# 07_Interface.net
KiCad netlist of a schematic drawn in Altium Designer
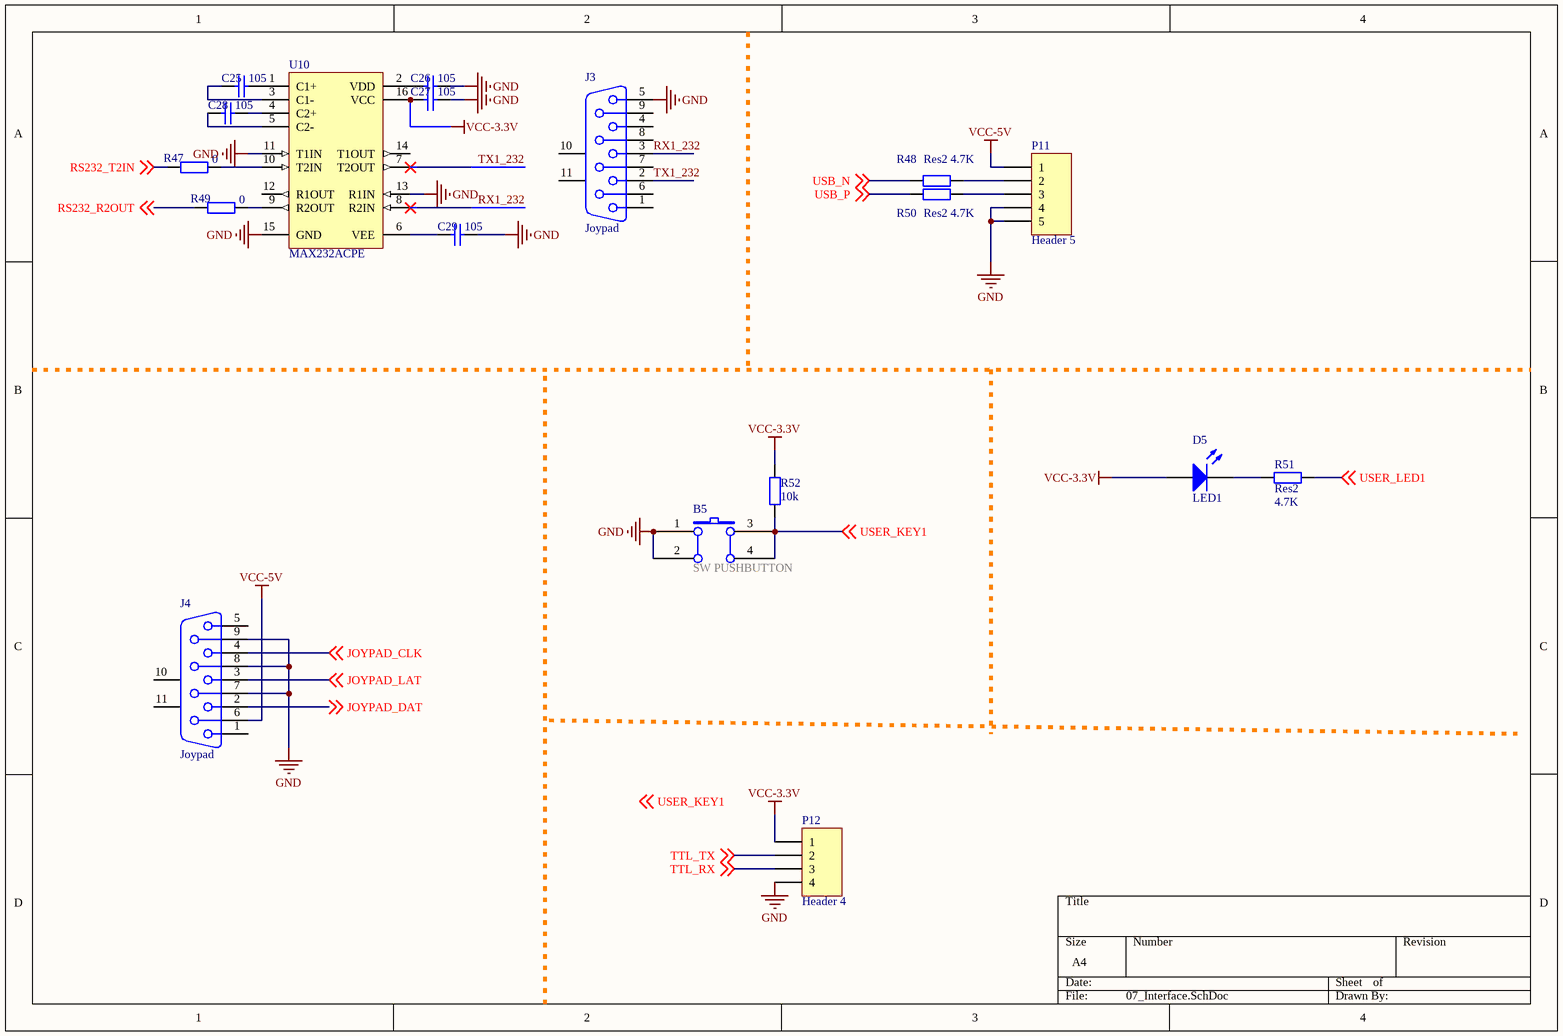
[diagram p0: 07_Interface.SchDoc]

(export (version "E")
  (design (tool "Eeschema 10.0.6"))
  (components
    (comp (ref "B5")
      (value "SW PUSHBUTTON")
      (footprint "Miscellaneous Modules:SWITCH-0.65/0.45")
      (description "Tactile Switch")
      (libsource (lib "Miscellaneous Modules") (part "SW PUSHBUTTON"))
    )
    (comp (ref "C25")
      (value "105")
      (footprint "RAD-0.1")
      (description "Capacitor")
      (fields (field (name "PUBLISHER") "Altium Limited"))
      (libsource (lib "HLK-RM04_KIT-V2.3") (part "Cap"))
    )
    (comp (ref "C26")
      (value "105")
      (footprint "RAD-0.1")
      (description "Capacitor")
      (fields (field (name "PUBLISHER") "Altium Limited"))
      (libsource (lib "HLK-RM04_KIT-V2.3") (part "Cap"))
    )
    (comp (ref "C27")
      (value "105")
      (footprint "RAD-0.1")
      (description "Capacitor")
      (fields (field (name "PUBLISHER") "Altium Limited"))
      (libsource (lib "HLK-RM04_KIT-V2.3") (part "Cap"))
    )
    (comp (ref "C28")
      (value "105")
      (footprint "RAD-0.1")
      (description "Capacitor")
      (fields (field (name "PUBLISHER") "Altium Limited"))
      (libsource (lib "HLK-RM04_KIT-V2.3") (part "Cap"))
    )
    (comp (ref "C29")
      (value "105")
      (footprint "RAD-0.1")
      (description "Capacitor")
      (fields (field (name "PUBLISHER") "Altium Limited"))
      (libsource (lib "HLK-RM04_KIT-V2.3") (part "Cap"))
    )
    (comp (ref "D5")
      (value "LED1")
      (footprint "LED-R3.0")
      (description "Typical RED GaAs LED")
      (fields (field (name "PUBLISHER") "Altium Limited"))
      (libsource (lib "Miscellaneous Devices") (part "LED1"))
    )
    (comp (ref "J3")
      (value "Joypad")
      (footprint "DSUB1.385-2H9")
      (description "Receptacle Assembly, 9 Position, Right Angle")
      (fields (field (name "PUBLISHER") "Altium Limited"))
      (libsource (lib "Miscellaneous Connectors") (part "D Connector 9"))
    )
    (comp (ref "J4")
      (value "Joypad")
      (footprint "DSUB1.385-2H9")
      (description "Receptacle Assembly, 9 Position, Right Angle")
      (fields (field (name "PUBLISHER") "Altium Limited"))
      (libsource (lib "Miscellaneous Connectors") (part "D Connector 9"))
    )
    (comp (ref "P11")
      (value "Header 5")
      (footprint "MICRO_USB")
      (description "Header, 5-Pin")
      (fields (field (name "PUBLISHER") "Altium Limited"))
      (libsource (lib "Miscellaneous Connectors") (part "Header 5"))
    )
    (comp (ref "P12")
      (value "Header 4")
      (footprint "HDR1X4")
      (description "Header, 4-Pin")
      (fields (field (name "PUBLISHER") "Altium Limited"))
      (libsource (lib "Miscellaneous Connectors") (part "Header 4"))
    )
    (comp (ref "R47")
      (value "0")
      (footprint "AXIAL-0.3")
      (description "Resistor")
      (fields (field (name "PUBLISHER") "Altium Limited"))
      (libsource (lib "HLK-RM04_KIT-V2.3") (part "Res2"))
    )
    (comp (ref "R48")
      (value "Res2")
      (footprint "AXIAL-0.3")
      (description "Resistor")
      (fields (field (name "ALTIUM_VALUE") "4.7K") (field (name "PUBLISHER") "Altium Limited"))
      (libsource (lib "Miscellaneous Devices") (part "Res2"))
    )
    (comp (ref "R49")
      (value "0")
      (footprint "AXIAL-0.3")
      (description "Resistor")
      (fields (field (name "PUBLISHER") "Altium Limited"))
      (libsource (lib "HLK-RM04_KIT-V2.3") (part "Res2"))
    )
    (comp (ref "R50")
      (value "Res2")
      (footprint "AXIAL-0.3")
      (description "Resistor")
      (fields (field (name "ALTIUM_VALUE") "4.7K") (field (name "PUBLISHER") "Altium Limited"))
      (libsource (lib "Miscellaneous Devices") (part "Res2"))
    )
    (comp (ref "R51")
      (value "Res2")
      (footprint "AXIAL-0.3")
      (description "Resistor")
      (fields (field (name "ALTIUM_VALUE") "4.7K") (field (name "PUBLISHER") "Altium Limited"))
      (libsource (lib "Miscellaneous Devices") (part "Res2"))
    )
    (comp (ref "R52")
      (value "10k")
      (footprint "AXIAL-0.3")
      (description "贴片电阻")
      (fields (field (name "PUBLISHER") "Altium Limited"))
      (libsource (lib "fszhang") (part "Res1"))
    )
    (comp (ref "U10")
      (value "MAX232ACPE")
      (footprint "SO-16_M")
      (description "+5V Powered, Multi-Channel RS-232 Driver/Receiver")
      (fields (field (name "PUBLISHER") "Altium Limited"))
      (libsource (lib "HLK-RM04_KIT-V2.3") (part "MAX232ACPE"))
    )
  )
  (nets
    (net (code "1") (name "/RX1_232") (class "Default")
      (node (ref "J3") (pin "3") (pinfunction "3_3") (pintype "passive"))
      (node (ref "U10") (pin "8") (pinfunction "R2IN_8") (pintype "input"))
    )
    (net (code "2") (name "/TX1_232") (class "Default")
      (node (ref "J3") (pin "2") (pinfunction "2_2") (pintype "passive"))
      (node (ref "U10") (pin "7") (pinfunction "T2OUT_7") (pintype "output"))
    )
    (net (code "3") (name "GND") (class "Default")
      (node (ref "B5") (pin "1") (pinfunction "A0_1") (pintype "passive"))
      (node (ref "B5") (pin "2") (pinfunction "B0_2") (pintype "passive"))
      (node (ref "C26") (pin "2") (pinfunction "2_2") (pintype "passive"))
      (node (ref "C27") (pin "2") (pinfunction "2_2") (pintype "passive"))
      (node (ref "C29") (pin "2") (pinfunction "2_2") (pintype "passive"))
      (node (ref "J3") (pin "5") (pinfunction "5_5") (pintype "passive"))
      (node (ref "J4") (pin "7") (pinfunction "7_7") (pintype "passive"))
      (node (ref "J4") (pin "8") (pinfunction "8_8") (pintype "passive"))
      (node (ref "J4") (pin "9") (pinfunction "9_9") (pintype "passive"))
      (node (ref "P11") (pin "4") (pinfunction "4_4") (pintype "passive"))
      (node (ref "P11") (pin "5") (pinfunction "5_5") (pintype "passive"))
      (node (ref "P12") (pin "4") (pinfunction "4_4") (pintype "passive"))
      (node (ref "U10") (pin "11") (pinfunction "T1IN_11") (pintype "input"))
      (node (ref "U10") (pin "13") (pinfunction "R1IN_13") (pintype "input"))
      (node (ref "U10") (pin "15") (pinfunction "GND_15") (pintype "power_in"))
    )
    (net (code "4") (name "JOYPAD_CLK") (class "Default")
      (node (ref "J4") (pin "4") (pinfunction "4_4") (pintype "passive"))
    )
    (net (code "5") (name "JOYPAD_DAT") (class "Default")
      (node (ref "J4") (pin "2") (pinfunction "2_2") (pintype "passive"))
    )
    (net (code "6") (name "JOYPAD_LAT") (class "Default")
      (node (ref "J4") (pin "3") (pinfunction "3_3") (pintype "passive"))
    )
    (net (code "7") (name "Net-(D5-K)") (class "Default")
      (node (ref "D5") (pin "2") (pinfunction "K_2") (pintype "passive"))
      (node (ref "R51") (pin "2") (pinfunction "2_2") (pintype "passive"))
    )
    (net (code "8") (name "Net-(P11-Pad2)") (class "Default")
      (node (ref "P11") (pin "2") (pinfunction "2_2") (pintype "passive"))
      (node (ref "R48") (pin "1") (pinfunction "1_1") (pintype "passive"))
    )
    (net (code "9") (name "Net-(P11-Pad3)") (class "Default")
      (node (ref "P11") (pin "3") (pinfunction "3_3") (pintype "passive"))
      (node (ref "R50") (pin "1") (pinfunction "1_1") (pintype "passive"))
    )
    (net (code "10") (name "Net-(U10-C1+)") (class "Default")
      (node (ref "C25") (pin "2") (pinfunction "2_2") (pintype "passive"))
      (node (ref "U10") (pin "1") (pinfunction "C1+_1") (pintype "passive"))
    )
    (net (code "11") (name "Net-(U10-C1-)") (class "Default")
      (node (ref "C25") (pin "1") (pinfunction "1_1") (pintype "passive"))
      (node (ref "U10") (pin "3") (pinfunction "C1-_3") (pintype "passive"))
    )
    (net (code "12") (name "Net-(U10-C2+)") (class "Default")
      (node (ref "C28") (pin "2") (pinfunction "2_2") (pintype "passive"))
      (node (ref "U10") (pin "4") (pinfunction "C2+_4") (pintype "passive"))
    )
    (net (code "13") (name "Net-(U10-C2-)") (class "Default")
      (node (ref "C28") (pin "1") (pinfunction "1_1") (pintype "passive"))
      (node (ref "U10") (pin "5") (pinfunction "C2-_5") (pintype "passive"))
    )
    (net (code "14") (name "Net-(U10-R2OUT)") (class "Default")
      (node (ref "R49") (pin "2") (pinfunction "2_2") (pintype "passive"))
      (node (ref "U10") (pin "9") (pinfunction "R2OUT_9") (pintype "output"))
    )
    (net (code "15") (name "Net-(U10-T2IN)") (class "Default")
      (node (ref "R47") (pin "2") (pinfunction "2_2") (pintype "passive"))
      (node (ref "U10") (pin "10") (pinfunction "T2IN_10") (pintype "input"))
    )
    (net (code "16") (name "Net-(U10-VDD)") (class "Default")
      (node (ref "C26") (pin "1") (pinfunction "1_1") (pintype "passive"))
      (node (ref "U10") (pin "2") (pinfunction "VDD_2") (pintype "power_in"))
    )
    (net (code "17") (name "Net-(U10-VEE)") (class "Default")
      (node (ref "C29") (pin "1") (pinfunction "1_1") (pintype "passive"))
      (node (ref "U10") (pin "6") (pinfunction "VEE_6") (pintype "power_in"))
    )
    (net (code "18") (name "RS232_R2OUT") (class "Default")
      (node (ref "R49") (pin "1") (pinfunction "1_1") (pintype "passive"))
    )
    (net (code "19") (name "RS232_T2IN") (class "Default")
      (node (ref "R47") (pin "1") (pinfunction "1_1") (pintype "passive"))
    )
    (net (code "20") (name "TTL_RX") (class "Default")
      (node (ref "P12") (pin "3") (pinfunction "3_3") (pintype "passive"))
    )
    (net (code "21") (name "TTL_TX") (class "Default")
      (node (ref "P12") (pin "2") (pinfunction "2_2") (pintype "passive"))
    )
    (net (code "22") (name "USB_N") (class "Default")
      (node (ref "R48") (pin "2") (pinfunction "2_2") (pintype "passive"))
    )
    (net (code "23") (name "USB_P") (class "Default")
      (node (ref "R50") (pin "2") (pinfunction "2_2") (pintype "passive"))
    )
    (net (code "24") (name "USER_KEY1") (class "Default")
      (node (ref "B5") (pin "3") (pinfunction "B1_3") (pintype "passive"))
      (node (ref "B5") (pin "4") (pinfunction "A1_4") (pintype "passive"))
      (node (ref "R52") (pin "1") (pinfunction "1_1") (pintype "passive"))
    )
    (net (code "25") (name "USER_LED1") (class "Default")
      (node (ref "R51") (pin "1") (pinfunction "1_1") (pintype "passive"))
    )
    (net (code "26") (name "VCC-3.3V") (class "Default")
      (node (ref "C27") (pin "1") (pinfunction "1_1") (pintype "passive"))
      (node (ref "D5") (pin "1") (pinfunction "A_1") (pintype "passive"))
      (node (ref "P12") (pin "1") (pinfunction "1_1") (pintype "passive"))
      (node (ref "R52") (pin "2") (pinfunction "2_2") (pintype "passive"))
      (node (ref "U10") (pin "16") (pinfunction "VCC_16") (pintype "power_in"))
    )
    (net (code "27") (name "VCC-5V") (class "Default")
      (node (ref "J4") (pin "6") (pinfunction "6_6") (pintype "passive"))
      (node (ref "P11") (pin "1") (pinfunction "1_1") (pintype "passive"))
    )
    (net (code "28") (name "unconnected-(J3-MH1-Pad10)") (class "Default")
      (node (ref "J3") (pin "10") (pinfunction "MH1_10") (pintype "passive"))
    )
    (net (code "29") (name "unconnected-(J3-MH2-Pad11)") (class "Default")
      (node (ref "J3") (pin "11") (pinfunction "MH2_11") (pintype "passive"))
    )
    (net (code "30") (name "unconnected-(J3-Pad1)") (class "Default")
      (node (ref "J3") (pin "1") (pinfunction "1_1") (pintype "passive"))
    )
    (net (code "31") (name "unconnected-(J3-Pad4)") (class "Default")
      (node (ref "J3") (pin "4") (pinfunction "4_4") (pintype "passive"))
    )
    (net (code "32") (name "unconnected-(J3-Pad6)") (class "Default")
      (node (ref "J3") (pin "6") (pinfunction "6_6") (pintype "passive"))
    )
    (net (code "33") (name "unconnected-(J3-Pad7)") (class "Default")
      (node (ref "J3") (pin "7") (pinfunction "7_7") (pintype "passive"))
    )
    (net (code "34") (name "unconnected-(J3-Pad8)") (class "Default")
      (node (ref "J3") (pin "8") (pinfunction "8_8") (pintype "passive"))
    )
    (net (code "35") (name "unconnected-(J3-Pad9)") (class "Default")
      (node (ref "J3") (pin "9") (pinfunction "9_9") (pintype "passive"))
    )
    (net (code "36") (name "unconnected-(J4-MH1-Pad10)") (class "Default")
      (node (ref "J4") (pin "10") (pinfunction "MH1_10") (pintype "passive"))
    )
    (net (code "37") (name "unconnected-(J4-MH2-Pad11)") (class "Default")
      (node (ref "J4") (pin "11") (pinfunction "MH2_11") (pintype "passive"))
    )
    (net (code "38") (name "unconnected-(J4-Pad1)") (class "Default")
      (node (ref "J4") (pin "1") (pinfunction "1_1") (pintype "passive"))
    )
    (net (code "39") (name "unconnected-(J4-Pad5)") (class "Default")
      (node (ref "J4") (pin "5") (pinfunction "5_5") (pintype "passive"))
    )
    (net (code "40") (name "unconnected-(U10-R1OUT-Pad12)") (class "Default")
      (node (ref "U10") (pin "12") (pinfunction "R1OUT_12") (pintype "output"))
    )
    (net (code "41") (name "unconnected-(U10-T1OUT-Pad14)") (class "Default")
      (node (ref "U10") (pin "14") (pinfunction "T1OUT_14") (pintype "output"))
    )
  )
)
